# AGSE_Motor_Controller.net
KiCad netlist of a schematic drawn in EAGLE
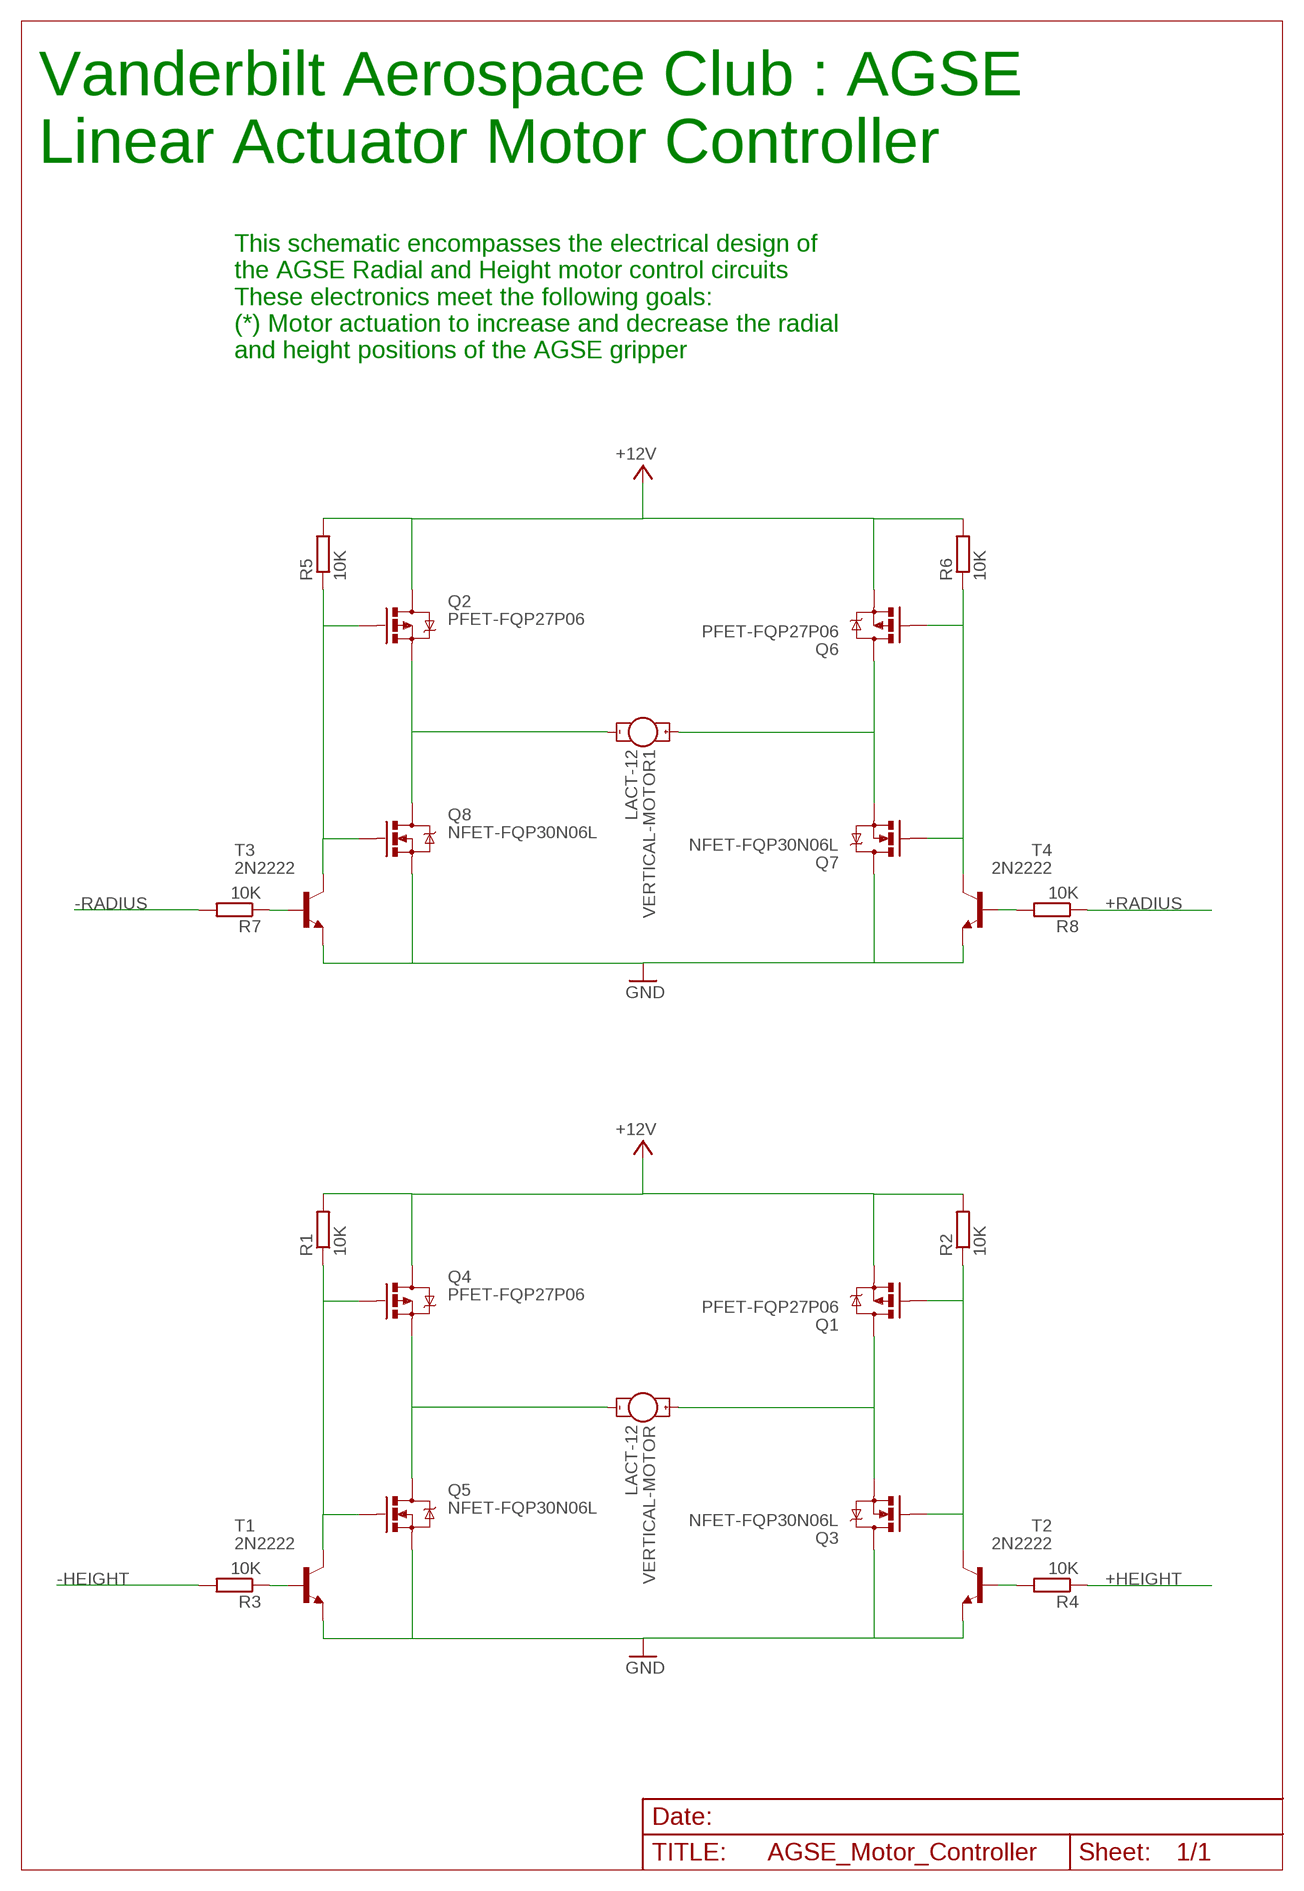
[diagram p0: schematic, sheet 1]

(export (version "E")
  (design (tool "Eeschema 10.0.6"))
  (components
    (comp (ref "Q1")
      (value "PFET-FQP27P06")
      (footprint "eagle-import:TO220V")
      (libsource (lib "eagle-import") (part "MOSFET-PCHANNELFQP27P06"))
    )
    (comp (ref "Q2")
      (value "PFET-FQP27P06")
      (footprint "eagle-import:TO220V")
      (libsource (lib "eagle-import") (part "MOSFET-PCHANNELFQP27P06"))
    )
    (comp (ref "Q3")
      (value "NFET-FQP30N06L")
      (footprint "eagle-import:TO220V")
      (libsource (lib "eagle-import") (part "MOSFET-NCHANNELFQP30N06L"))
    )
    (comp (ref "Q4")
      (value "PFET-FQP27P06")
      (footprint "eagle-import:TO220V")
      (libsource (lib "eagle-import") (part "MOSFET-PCHANNELFQP27P06"))
    )
    (comp (ref "Q5")
      (value "NFET-FQP30N06L")
      (footprint "eagle-import:TO220V")
      (libsource (lib "eagle-import") (part "MOSFET-NCHANNELFQP30N06L"))
    )
    (comp (ref "Q6")
      (value "PFET-FQP27P06")
      (footprint "eagle-import:TO220V")
      (libsource (lib "eagle-import") (part "MOSFET-PCHANNELFQP27P06"))
    )
    (comp (ref "Q7")
      (value "NFET-FQP30N06L")
      (footprint "eagle-import:TO220V")
      (libsource (lib "eagle-import") (part "MOSFET-NCHANNELFQP30N06L"))
    )
    (comp (ref "Q8")
      (value "NFET-FQP30N06L")
      (footprint "eagle-import:TO220V")
      (libsource (lib "eagle-import") (part "MOSFET-NCHANNELFQP30N06L"))
    )
    (comp (ref "R1")
      (value "10K")
      (footprint "eagle-import:0207_12")
      (libsource (lib "eagle-import") (part "R-EU_0207/12"))
    )
    (comp (ref "R2")
      (value "10K")
      (footprint "eagle-import:0207_12")
      (libsource (lib "eagle-import") (part "R-EU_0207/12"))
    )
    (comp (ref "R3")
      (value "10K")
      (footprint "eagle-import:0207_12")
      (libsource (lib "eagle-import") (part "R-EU_0207/12"))
    )
    (comp (ref "R4")
      (value "10K")
      (footprint "eagle-import:0207_12")
      (libsource (lib "eagle-import") (part "R-EU_0207/12"))
    )
    (comp (ref "R5")
      (value "10K")
      (footprint "eagle-import:0207_12")
      (libsource (lib "eagle-import") (part "R-EU_0207/12"))
    )
    (comp (ref "R6")
      (value "10K")
      (footprint "eagle-import:0207_12")
      (libsource (lib "eagle-import") (part "R-EU_0207/12"))
    )
    (comp (ref "R7")
      (value "10K")
      (footprint "eagle-import:0207_12")
      (libsource (lib "eagle-import") (part "R-EU_0207/12"))
    )
    (comp (ref "R8")
      (value "10K")
      (footprint "eagle-import:0207_12")
      (libsource (lib "eagle-import") (part "R-EU_0207/12"))
    )
    (comp (ref "T1")
      (value "2N2222")
      (footprint "eagle-import:TO18")
      (libsource (lib "eagle-import") (part "2N2222"))
    )
    (comp (ref "T2")
      (value "2N2222")
      (footprint "eagle-import:TO18")
      (libsource (lib "eagle-import") (part "2N2222"))
    )
    (comp (ref "T3")
      (value "2N2222")
      (footprint "eagle-import:TO18")
      (libsource (lib "eagle-import") (part "2N2222"))
    )
    (comp (ref "T4")
      (value "2N2222")
      (footprint "eagle-import:TO18")
      (libsource (lib "eagle-import") (part "2N2222"))
    )
    (comp (ref "VERTICAL-MOTOR")
      (value "LACT-12")
      (footprint "eagle-import:VIBE-MOTOR-10MM")
      (libsource (lib "eagle-import") (part "MOTOR10MM"))
    )
    (comp (ref "VERTICAL-MOTOR1")
      (value "LACT-12")
      (footprint "eagle-import:VIBE-MOTOR-10MM")
      (libsource (lib "eagle-import") (part "MOTOR10MM"))
    )
  )
  (nets
    (net (code "1") (name "+12V") (class "Default")
      (node (ref "Q1") (pin "3") (pinfunction "S_3") (pintype "passive"))
      (node (ref "Q2") (pin "2") (pinfunction "D_2") (pintype "passive"))
      (node (ref "Q4") (pin "2") (pinfunction "D_2") (pintype "passive"))
      (node (ref "Q6") (pin "3") (pinfunction "S_3") (pintype "passive"))
      (node (ref "R1") (pin "2") (pinfunction "2_2") (pintype "passive"))
      (node (ref "R2") (pin "2") (pinfunction "2_2") (pintype "passive"))
      (node (ref "R5") (pin "2") (pinfunction "2_2") (pintype "passive"))
      (node (ref "R6") (pin "2") (pinfunction "2_2") (pintype "passive"))
    )
    (net (code "2") (name "/+HEIGHT") (class "Default")
      (node (ref "R4") (pin "1") (pinfunction "1_1") (pintype "passive"))
    )
    (net (code "3") (name "/+RADIUS") (class "Default")
      (node (ref "R8") (pin "1") (pinfunction "1_1") (pintype "passive"))
    )
    (net (code "4") (name "/-HEIGHT") (class "Default")
      (node (ref "R3") (pin "2") (pinfunction "2_2") (pintype "passive"))
    )
    (net (code "5") (name "/-RADIUS") (class "Default")
      (node (ref "R7") (pin "2") (pinfunction "2_2") (pintype "passive"))
    )
    (net (code "6") (name "GND") (class "Default")
      (node (ref "Q3") (pin "2") (pinfunction "D_2") (pintype "passive"))
      (node (ref "Q5") (pin "3") (pinfunction "S_3") (pintype "passive"))
      (node (ref "Q7") (pin "2") (pinfunction "D_2") (pintype "passive"))
      (node (ref "Q8") (pin "3") (pinfunction "S_3") (pintype "passive"))
      (node (ref "T1") (pin "1") (pinfunction "E_1") (pintype "passive"))
      (node (ref "T2") (pin "1") (pinfunction "E_1") (pintype "passive"))
      (node (ref "T3") (pin "1") (pinfunction "E_1") (pintype "passive"))
      (node (ref "T4") (pin "1") (pinfunction "E_1") (pintype "passive"))
    )
    (net (code "7") (name "Net-(Q1-D)") (class "Default")
      (node (ref "Q1") (pin "2") (pinfunction "D_2") (pintype "passive"))
      (node (ref "Q3") (pin "3") (pinfunction "S_3") (pintype "passive"))
      (node (ref "VERTICAL-MOTOR") (pin "+") (pinfunction "+_+") (pintype "bidirectional"))
    )
    (net (code "8") (name "Net-(Q1-G)") (class "Default")
      (node (ref "Q1") (pin "1") (pinfunction "G_1") (pintype "passive"))
      (node (ref "Q3") (pin "1") (pinfunction "G_1") (pintype "passive"))
      (node (ref "R2") (pin "1") (pinfunction "1_1") (pintype "passive"))
      (node (ref "T2") (pin "3") (pinfunction "C_3") (pintype "passive"))
    )
    (net (code "9") (name "Net-(Q2-G)") (class "Default")
      (node (ref "Q2") (pin "1") (pinfunction "G_1") (pintype "passive"))
      (node (ref "Q8") (pin "1") (pinfunction "G_1") (pintype "passive"))
      (node (ref "R5") (pin "1") (pinfunction "1_1") (pintype "passive"))
      (node (ref "T3") (pin "3") (pinfunction "C_3") (pintype "passive"))
    )
    (net (code "10") (name "Net-(Q2-S)") (class "Default")
      (node (ref "Q2") (pin "3") (pinfunction "S_3") (pintype "passive"))
      (node (ref "Q8") (pin "2") (pinfunction "D_2") (pintype "passive"))
      (node (ref "VERTICAL-MOTOR1") (pin "-") (pinfunction "-_-") (pintype "bidirectional"))
    )
    (net (code "11") (name "Net-(Q4-G)") (class "Default")
      (node (ref "Q4") (pin "1") (pinfunction "G_1") (pintype "passive"))
      (node (ref "Q5") (pin "1") (pinfunction "G_1") (pintype "passive"))
      (node (ref "R1") (pin "1") (pinfunction "1_1") (pintype "passive"))
      (node (ref "T1") (pin "3") (pinfunction "C_3") (pintype "passive"))
    )
    (net (code "12") (name "Net-(Q4-S)") (class "Default")
      (node (ref "Q4") (pin "3") (pinfunction "S_3") (pintype "passive"))
      (node (ref "Q5") (pin "2") (pinfunction "D_2") (pintype "passive"))
      (node (ref "VERTICAL-MOTOR") (pin "-") (pinfunction "-_-") (pintype "bidirectional"))
    )
    (net (code "13") (name "Net-(Q6-D)") (class "Default")
      (node (ref "Q6") (pin "2") (pinfunction "D_2") (pintype "passive"))
      (node (ref "Q7") (pin "3") (pinfunction "S_3") (pintype "passive"))
      (node (ref "VERTICAL-MOTOR1") (pin "+") (pinfunction "+_+") (pintype "bidirectional"))
    )
    (net (code "14") (name "Net-(Q6-G)") (class "Default")
      (node (ref "Q6") (pin "1") (pinfunction "G_1") (pintype "passive"))
      (node (ref "Q7") (pin "1") (pinfunction "G_1") (pintype "passive"))
      (node (ref "R6") (pin "1") (pinfunction "1_1") (pintype "passive"))
      (node (ref "T4") (pin "3") (pinfunction "C_3") (pintype "passive"))
    )
    (net (code "15") (name "Net-(T1-B)") (class "Default")
      (node (ref "R3") (pin "1") (pinfunction "1_1") (pintype "passive"))
      (node (ref "T1") (pin "2") (pinfunction "B_2") (pintype "passive"))
    )
    (net (code "16") (name "Net-(T2-B)") (class "Default")
      (node (ref "R4") (pin "2") (pinfunction "2_2") (pintype "passive"))
      (node (ref "T2") (pin "2") (pinfunction "B_2") (pintype "passive"))
    )
    (net (code "17") (name "Net-(T3-B)") (class "Default")
      (node (ref "R7") (pin "1") (pinfunction "1_1") (pintype "passive"))
      (node (ref "T3") (pin "2") (pinfunction "B_2") (pintype "passive"))
    )
    (net (code "18") (name "Net-(T4-B)") (class "Default")
      (node (ref "R8") (pin "2") (pinfunction "2_2") (pintype "passive"))
      (node (ref "T4") (pin "2") (pinfunction "B_2") (pintype "passive"))
    )
  )
)
